# Main.net
KiCad netlist of a schematic drawn in Altium Designer
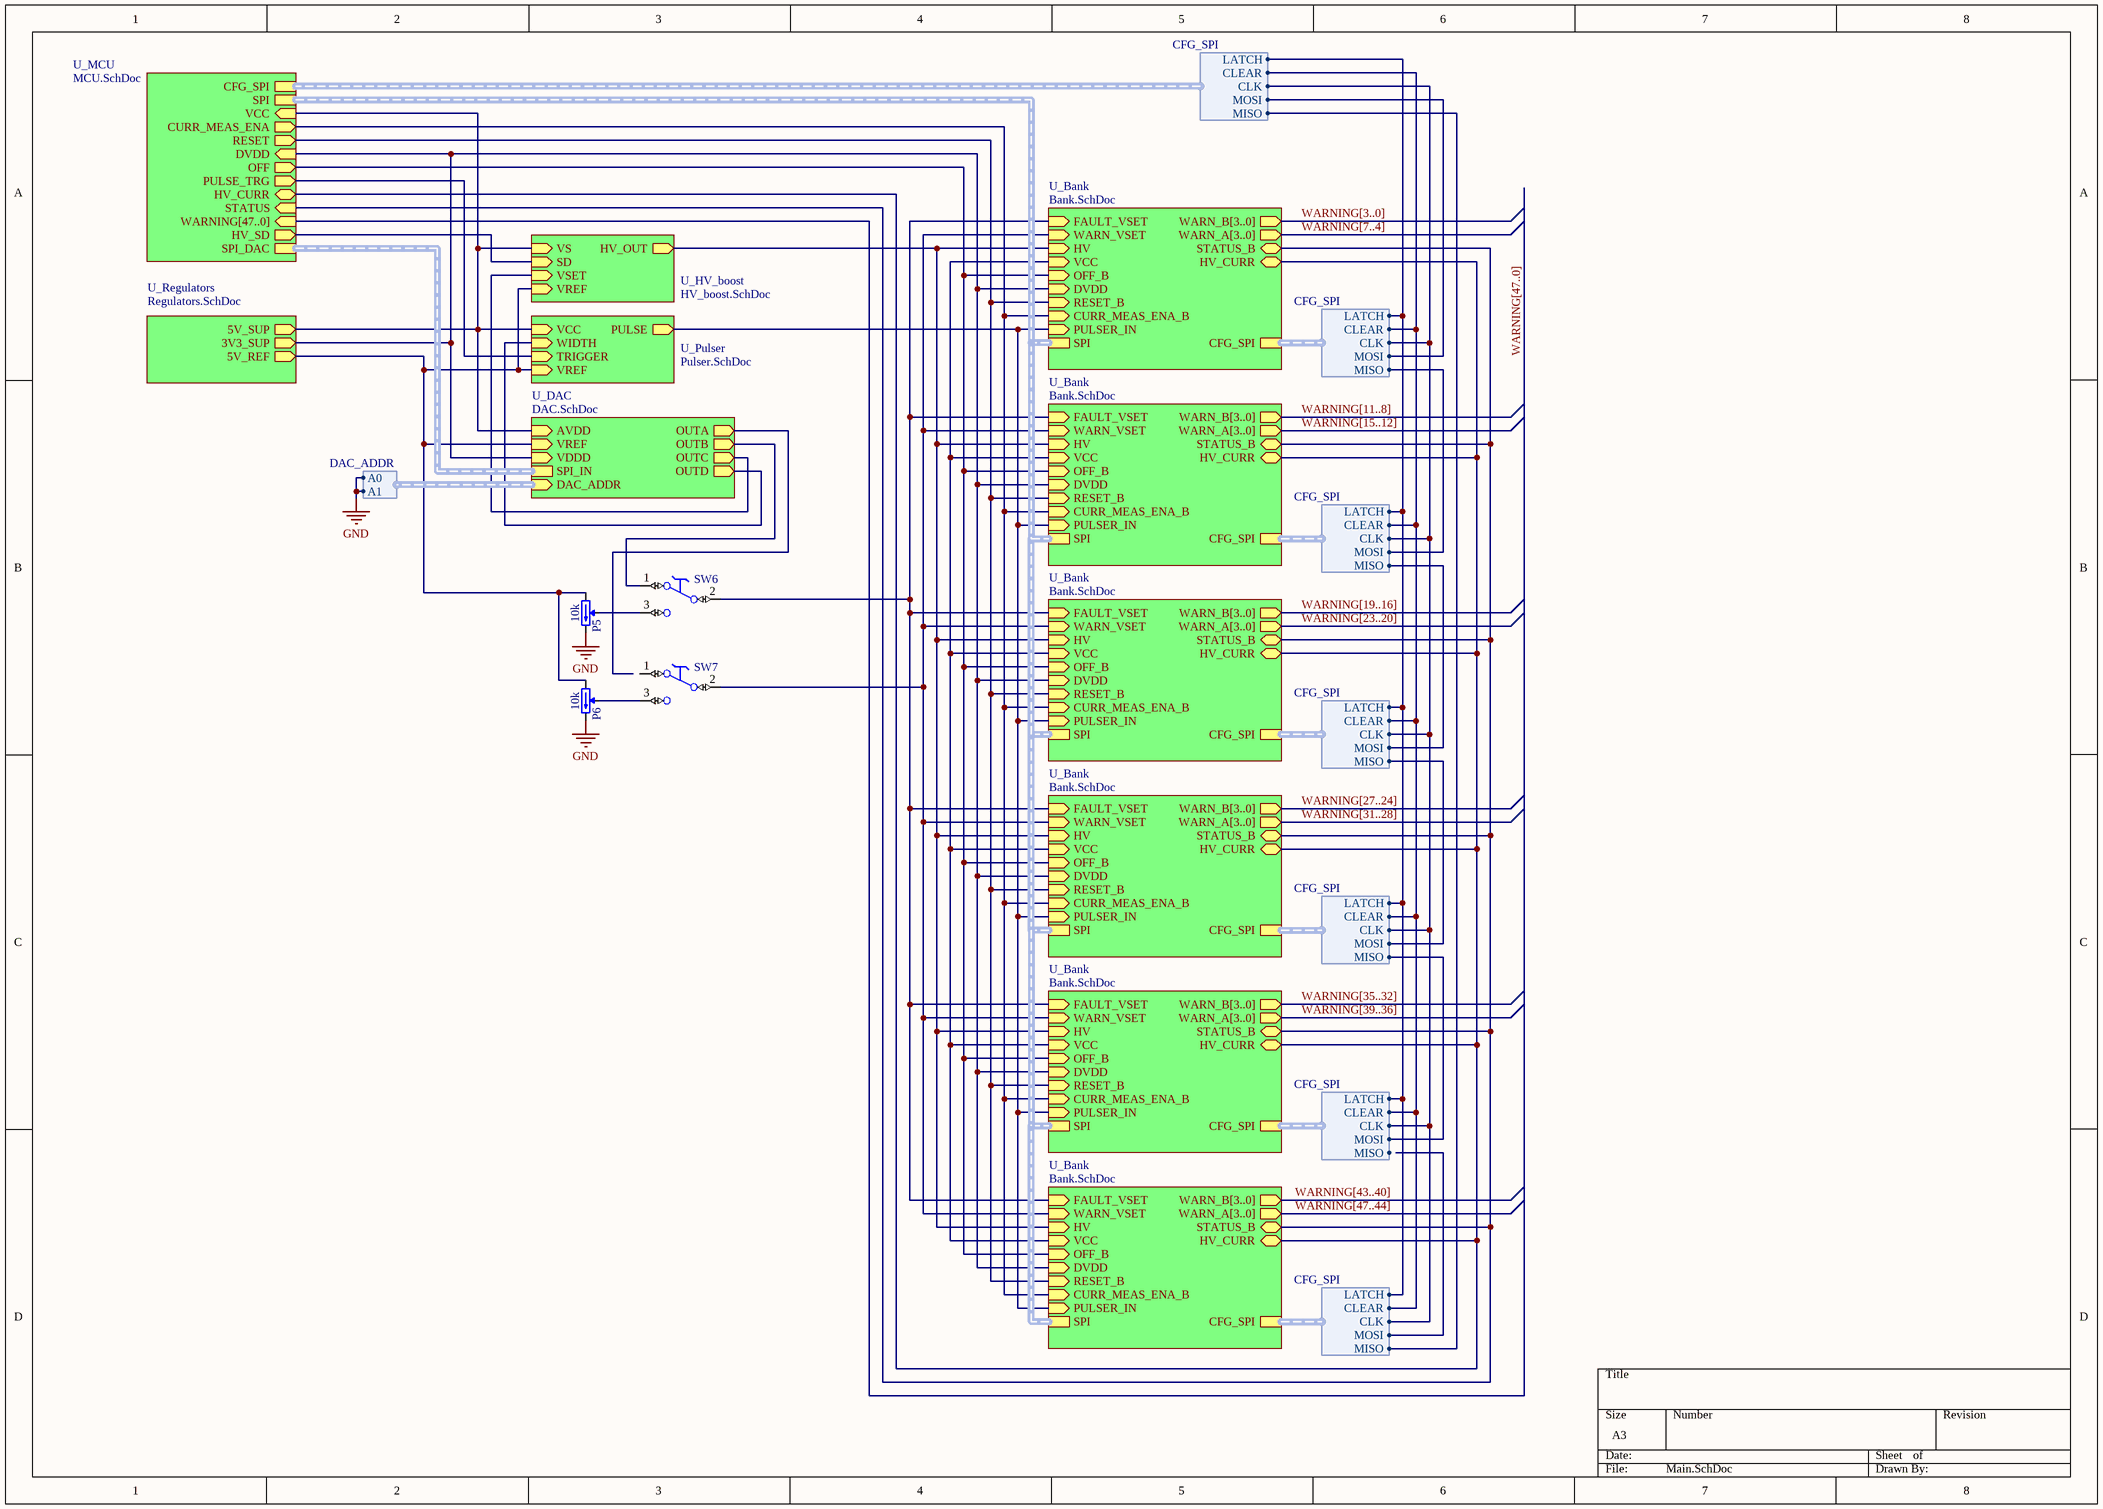
[diagram p0: Main.SchDoc]

(export (version "E")
  (design (tool "Eeschema 10.0.6"))
  (components
    (comp (ref "P5")
      (value "10k")
      (footprint "TRIM_BOURNS_3266W")
      (description "Trimming Potentiometer")
      (fields
        (field (name "PART NUMBER") "TRIM_12T_10K_BOURNS_3266W-1-103LF")
        (field (name "POWER") "0.25W")
        (field (name "AUTHOR") "CERN DEM JLC")
      )
      (libsource (lib "Resistors") (part "Trimming Potentiometer"))
    )
    (comp (ref "P6")
      (value "10k")
      (footprint "TRIM_BOURNS_3266W")
      (description "Trimming Potentiometer")
      (fields
        (field (name "PART NUMBER") "TRIM_12T_10K_BOURNS_3266W-1-103LF")
        (field (name "POWER") "0.25W")
        (field (name "AUTHOR") "CERN DEM JLC")
      )
      (libsource (lib "Resistors") (part "Trimming Potentiometer"))
    )
    (comp (ref "SW6")
      (value "Switch")
      (footprint "SW_TYCO_1-1437575-4")
      (description "SPDT Switch")
      (fields
        (field (name "PART NUMBER") "SW_TYCO_1-1437575-4")
        (field (name "MANUFACTURER") "TYCO")
        (field (name "AUTHOR") "CERN DEM JLC")
      )
      (libsource (lib "Eletro-mechanical") (part "SW SPDT 1NC-2C-3NO"))
    )
    (comp (ref "SW7")
      (value "Switch")
      (footprint "SW_TYCO_1-1437575-4")
      (description "SPDT Switch")
      (fields
        (field (name "PART NUMBER") "SW_TYCO_1-1437575-4")
        (field (name "MANUFACTURER") "TYCO")
        (field (name "AUTHOR") "CERN DEM JLC")
      )
      (libsource (lib "Eletro-mechanical") (part "SW SPDT 1NC-2C-3NO"))
    )
  )
  (nets
    (net (code "52") (name "/5V_REF") (class "Default")
      (node (ref "P5") (pin "1") (pinfunction "CCW_1") (pintype "passive"))
      (node (ref "P6") (pin "1") (pinfunction "CCW_1") (pintype "passive"))
    )
    (net (code "55") (name "/FAULT_VSET") (class "Default")
      (node (ref "SW6") (pin "2") (pinfunction "C_2") (pintype "bidirectional"))
    )
    (net (code "61") (name "/OUTB") (class "Default")
      (node (ref "SW6") (pin "1") (pinfunction "NC_1") (pintype "bidirectional"))
    )
    (net (code "84") (name "/WARN_VSET") (class "Default")
      (node (ref "SW7") (pin "2") (pinfunction "C_2") (pintype "bidirectional"))
    )
    (net (code "87") (name "GND") (class "Default")
      (node (ref "P5") (pin "3") (pinfunction "CW_3") (pintype "passive"))
      (node (ref "P6") (pin "3") (pinfunction "CW_3") (pintype "passive"))
    )
    (net (code "88") (name "Net-(P5-W)") (class "Default")
      (node (ref "P5") (pin "2") (pinfunction "W_2") (pintype "passive"))
      (node (ref "SW6") (pin "3") (pinfunction "NO_3") (pintype "bidirectional"))
    )
    (net (code "89") (name "Net-(P6-W)") (class "Default")
      (node (ref "P6") (pin "2") (pinfunction "W_2") (pintype "passive"))
      (node (ref "SW7") (pin "3") (pinfunction "NO_3") (pintype "bidirectional"))
    )
    (net (code "90") (name "unconnected-(SW7-NC-Pad1)") (class "Default")
      (node (ref "SW7") (pin "1") (pinfunction "NC_1") (pintype "bidirectional"))
    )
  )
)
